# Analiser.net
KiCad netlist of a schematic drawn in Altium Designer
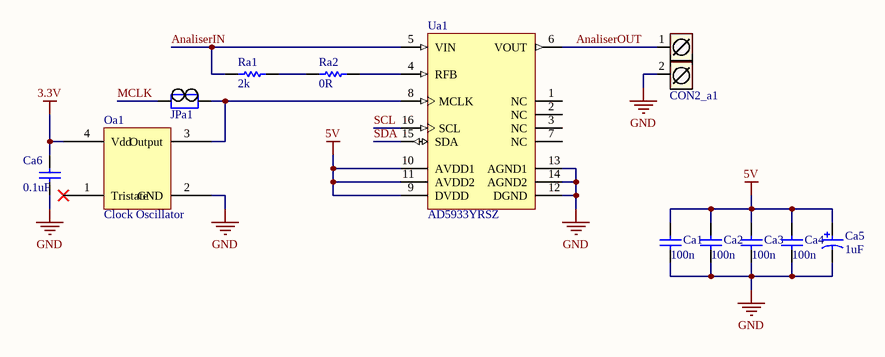
[diagram p0: Analiser.SchDoc]

(export (version "E")
  (design (tool "Eeschema 10.0.6"))
  (components
    (comp (ref "Ca1")
      (value "100n")
      (footprint "CAPC0603(1608)100_L")
      (description "0603 (1608 Metric) Chip Capacitor")
      (libsource (lib "Altium Content Vault") (part "CAP_5"))
    )
    (comp (ref "Ca2")
      (value "100n")
      (footprint "CAPC0603(1608)100_L")
      (description "0603 (1608 Metric) Chip Capacitor")
      (libsource (lib "Altium Content Vault") (part "CAP_5"))
    )
    (comp (ref "Ca3")
      (value "100n")
      (footprint "CAPC0603(1608)100_L")
      (description "0603 (1608 Metric) Chip Capacitor")
      (libsource (lib "Altium Content Vault") (part "CAP_5"))
    )
    (comp (ref "Ca4")
      (value "100n")
      (footprint "CAPC0603(1608)100_L")
      (description "0603 (1608 Metric) Chip Capacitor")
      (libsource (lib "Altium Content Vault") (part "CAP_5"))
    )
    (comp (ref "Ca5")
      (value "1uF")
      (footprint "CAPMP3217X18-T_V")
      (description "Standard Tantalum, 1 uF, +/- 10%, 35 V, -55 to 125 degC, 2-Pin SMD (1206), RoHS, Tape and Reel")
      (libsource (lib "Altium Content Vault") (part "CAP-P-2"))
    )
    (comp (ref "Ca6")
      (value "0.1uF")
      (footprint "CAPC0603(1608)100_L")
      (description "0603 (1608 Metric) Chip Capacitor")
      (libsource (lib "Altium Content Vault") (part "CAP_5"))
    )
    (comp (ref "CON2_a1")
      (value "ARK2")
      (footprint "ARK2")
      (description "Złącze śrubowe 2 piny")
      (libsource (lib "Library_Altium") (part "ARK2"))
    )
    (comp (ref "JPa1")
      (value "Jumper")
      (footprint "HDR1X2 - JP")
      (description "Jumper, 2-Pin")
      (libsource (lib "Library_Altium") (part "Jumper_2"))
    )
    (comp (ref "Oa1")
      (value "Clock Oscillator")
      (footprint "Oscillator SMD")
      (description "1.8MHz Clock Source SMD")
      (libsource (lib "Own") (part "Clock Oscillator"))
    )
    (comp (ref "Ra1")
      (value "2k")
      (footprint "RESC0603(1608)_L")
      (description "0603 (1608 Metric) Chip Resistor")
      (libsource (lib "Altium Content Vault") (part "RES_3"))
    )
    (comp (ref "Ra2")
      (value "0R")
      (footprint "RESC0603(1608)_L")
      (description "0603 (1608 Metric) Chip Resistor")
      (libsource (lib "Altium Content Vault") (part "RES_3"))
    )
    (comp (ref "Ua1")
      (value "AD5933YRSZ")
      (footprint "ADI-RS-16_L")
      (description "1 MSPS, 12-Bit Impedance Converter, Network Analyzer, Serial, RS-16, 77 Tube, Pb-Free")
      (libsource (lib "Altium Content Vault") (part "ADI-AD5933-RS-16"))
    )
  )
  (nets
    (net (code "1") (name "/AnaliserIN") (class "Default")
      (node (ref "Ra1") (pin "1") (pinfunction "1_1") (pintype "passive"))
      (node (ref "Ua1") (pin "5") (pinfunction "VIN_5") (pintype "input"))
    )
    (net (code "2") (name "/AnaliserOUT") (class "Default")
      (node (ref "CON2_a1") (pin "1") (pinfunction "1_1") (pintype "passive"))
      (node (ref "Ua1") (pin "6") (pinfunction "VOUT_6") (pintype "output"))
    )
    (net (code "3") (name "/MCLK") (class "Default")
      (node (ref "JPa1") (pin "1") (pinfunction "1_1") (pintype "passive"))
    )
    (net (code "4") (name "/SCL") (class "Default")
      (node (ref "Ua1") (pin "16") (pinfunction "SCL_16") (pintype "input"))
    )
    (net (code "5") (name "/SDA") (class "Default")
      (node (ref "Ua1") (pin "15") (pinfunction "SDA_15") (pintype "bidirectional"))
    )
    (net (code "6") (name "3.3V") (class "Default")
      (node (ref "Ca6") (pin "2") (pinfunction "2_2") (pintype "passive"))
      (node (ref "Oa1") (pin "4") (pinfunction "Vdd_4") (pintype "passive"))
    )
    (net (code "7") (name "5V") (class "Default")
      (node (ref "Ca1") (pin "2") (pinfunction "2_2") (pintype "passive"))
      (node (ref "Ca2") (pin "2") (pinfunction "2_2") (pintype "passive"))
      (node (ref "Ca3") (pin "2") (pinfunction "2_2") (pintype "passive"))
      (node (ref "Ca4") (pin "2") (pinfunction "2_2") (pintype "passive"))
      (node (ref "Ca5") (pin "1") (pinfunction "1_1") (pintype "passive"))
      (node (ref "Ua1") (pin "10") (pinfunction "AVDD1_10") (pintype "power_in"))
      (node (ref "Ua1") (pin "11") (pinfunction "AVDD2_11") (pintype "power_in"))
      (node (ref "Ua1") (pin "9") (pinfunction "DVDD_9") (pintype "power_in"))
    )
    (net (code "8") (name "GND") (class "Default")
      (node (ref "CON2_a1") (pin "2") (pinfunction "2_2") (pintype "passive"))
      (node (ref "Ca1") (pin "1") (pinfunction "1_1") (pintype "passive"))
      (node (ref "Ca2") (pin "1") (pinfunction "1_1") (pintype "passive"))
      (node (ref "Ca3") (pin "1") (pinfunction "1_1") (pintype "passive"))
      (node (ref "Ca4") (pin "1") (pinfunction "1_1") (pintype "passive"))
      (node (ref "Ca5") (pin "2") (pinfunction "2_2") (pintype "passive"))
      (node (ref "Ca6") (pin "1") (pinfunction "1_1") (pintype "passive"))
      (node (ref "Oa1") (pin "2") (pinfunction "GND_2") (pintype "passive"))
      (node (ref "Ua1") (pin "12") (pinfunction "DGND_12") (pintype "power_in"))
      (node (ref "Ua1") (pin "13") (pinfunction "AGND1_13") (pintype "power_in"))
      (node (ref "Ua1") (pin "14") (pinfunction "AGND2_14") (pintype "power_in"))
    )
    (net (code "9") (name "Net-(Oa1-Output)") (class "Default")
      (node (ref "JPa1") (pin "2") (pinfunction "2_2") (pintype "passive"))
      (node (ref "Oa1") (pin "3") (pinfunction "Output_3") (pintype "passive"))
      (node (ref "Ua1") (pin "8") (pinfunction "MCLK_8") (pintype "input"))
    )
    (net (code "10") (name "Net-(Ra1-Pad2)") (class "Default")
      (node (ref "Ra1") (pin "2") (pinfunction "2_2") (pintype "passive"))
      (node (ref "Ra2") (pin "1") (pinfunction "1_1") (pintype "passive"))
    )
    (net (code "11") (name "Net-(Ua1-RFB)") (class "Default")
      (node (ref "Ra2") (pin "2") (pinfunction "2_2") (pintype "passive"))
      (node (ref "Ua1") (pin "4") (pinfunction "RFB_4") (pintype "input"))
    )
    (net (code "12") (name "unconnected-(Oa1-Tristate-Pad1)") (class "Default")
      (node (ref "Oa1") (pin "1") (pinfunction "Tristate_1") (pintype "passive+no_connect"))
    )
    (net (code "13") (name "unconnected-(Ua1-NC-Pad1)") (class "Default")
      (node (ref "Ua1") (pin "1") (pinfunction "NC_1") (pintype "passive"))
    )
    (net (code "14") (name "unconnected-(Ua1-NC-Pad2)") (class "Default")
      (node (ref "Ua1") (pin "2") (pinfunction "NC_2") (pintype "passive"))
    )
    (net (code "15") (name "unconnected-(Ua1-NC-Pad3)") (class "Default")
      (node (ref "Ua1") (pin "3") (pinfunction "NC_3") (pintype "passive"))
    )
    (net (code "16") (name "unconnected-(Ua1-NC-Pad7)") (class "Default")
      (node (ref "Ua1") (pin "7") (pinfunction "NC_7") (pintype "passive"))
    )
  )
)
